# Driver_Converter.net
KiCad netlist of a schematic drawn in Altium Designer
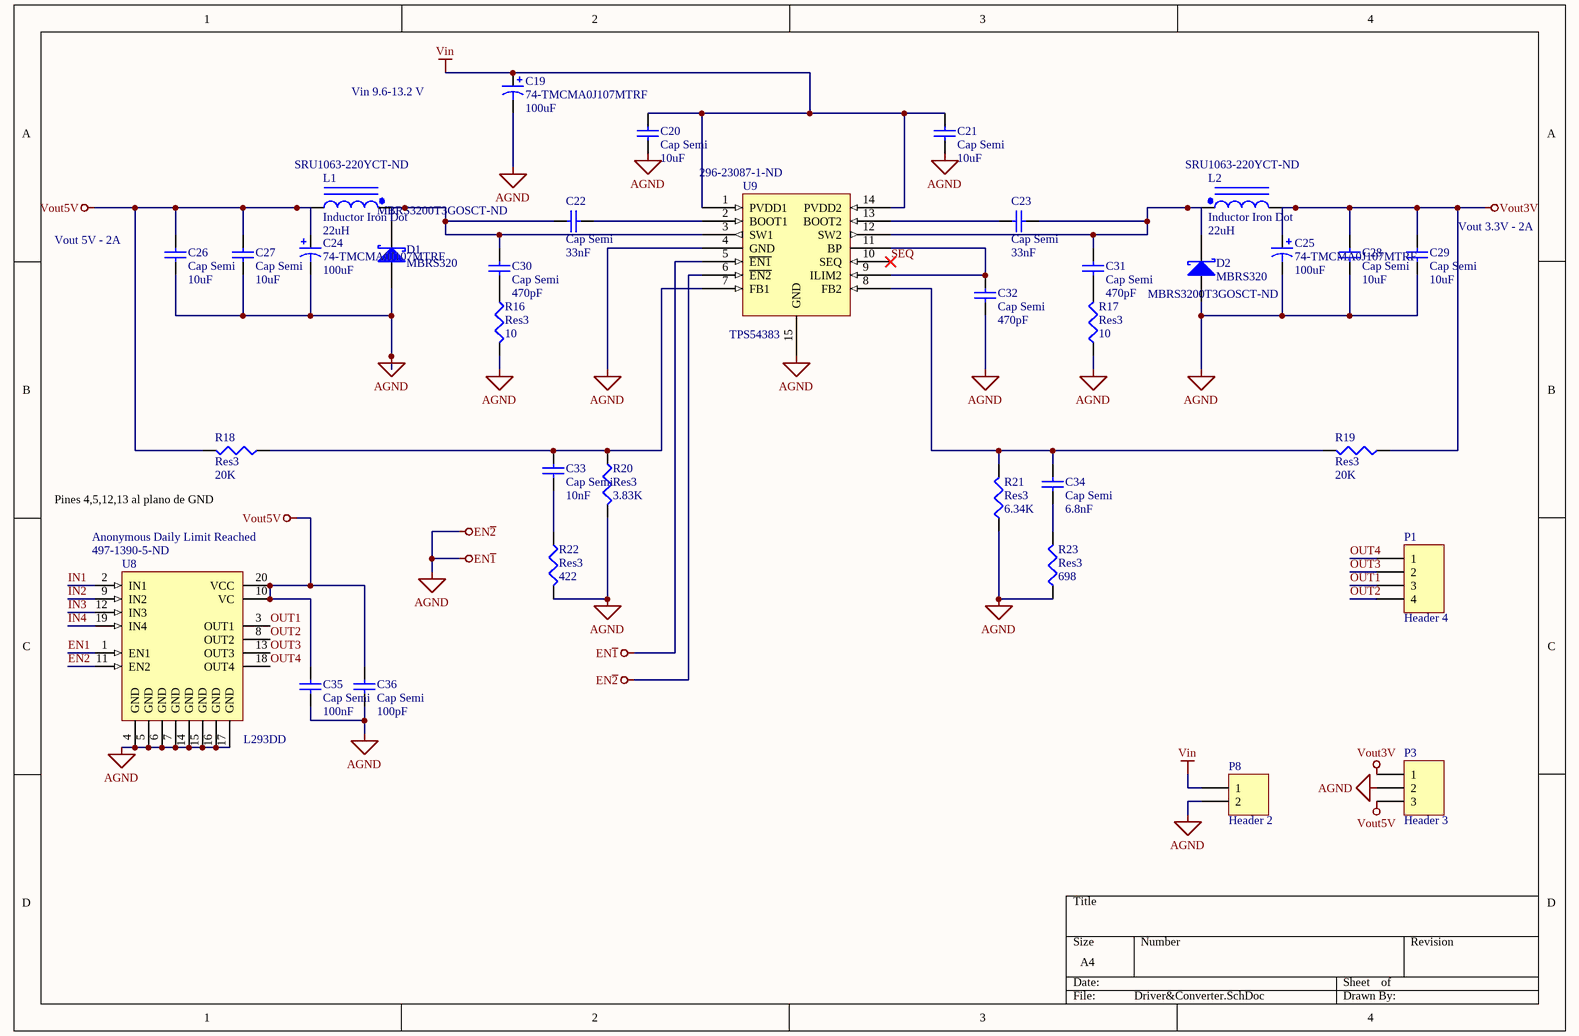
[diagram p0: Driver&Converter.SchDoc]

(export (version "E")
  (design (tool "Eeschema 10.0.6"))
  (components
    (comp (ref "C19")
      (value "74-TMCMA0J107MTRF")
      (footprint "C1206")
      (description "Polarized Capacitor (Surface Mount)")
      (fields (field (name "ALTIUM_VALUE") "100uF") (field (name "PUBLISHER") "Altium Limited"))
      (libsource (lib "Miscellaneous Devices") (part "Cap Pol3"))
    )
    (comp (ref "C20")
      (value "Cap Semi")
      (footprint "C1206")
      (description "Capacitor (Semiconductor SIM Model)")
      (fields (field (name "ALTIUM_VALUE") "10uF") (field (name "PUBLISHER") "Altium Limited"))
      (libsource (lib "Miscellaneous Devices") (part "Cap Semi"))
    )
    (comp (ref "C21")
      (value "Cap Semi")
      (footprint "C1206")
      (description "Capacitor (Semiconductor SIM Model)")
      (fields (field (name "ALTIUM_VALUE") "10uF") (field (name "PUBLISHER") "Altium Limited"))
      (libsource (lib "Miscellaneous Devices") (part "Cap Semi"))
    )
    (comp (ref "C22")
      (value "Cap Semi")
      (footprint "C1206")
      (description "Capacitor (Semiconductor SIM Model)")
      (fields (field (name "ALTIUM_VALUE") "33nF") (field (name "PUBLISHER") "Altium Limited"))
      (libsource (lib "Miscellaneous Devices") (part "Cap Semi"))
    )
    (comp (ref "C23")
      (value "Cap Semi")
      (footprint "C1206")
      (description "Capacitor (Semiconductor SIM Model)")
      (fields (field (name "ALTIUM_VALUE") "33nF") (field (name "PUBLISHER") "Altium Limited"))
      (libsource (lib "Miscellaneous Devices") (part "Cap Semi"))
    )
    (comp (ref "C24")
      (value "74-TMCMA0J107MTRF")
      (footprint "C1206")
      (description "Polarized Capacitor (Surface Mount)")
      (fields (field (name "ALTIUM_VALUE") "100uF") (field (name "PUBLISHER") "Altium Limited"))
      (libsource (lib "") (part "Cap Pol3_1"))
    )
    (comp (ref "C25")
      (value "74-TMCMA0J107MTRF")
      (footprint "C1206")
      (description "Polarized Capacitor (Surface Mount)")
      (fields (field (name "ALTIUM_VALUE") "100uF") (field (name "PUBLISHER") "Altium Limited"))
      (libsource (lib "Miscellaneous Devices") (part "Cap Pol3"))
    )
    (comp (ref "C26")
      (value "Cap Semi")
      (footprint "C1206")
      (description "Capacitor (Semiconductor SIM Model)")
      (fields (field (name "ALTIUM_VALUE") "10uF") (field (name "PUBLISHER") "Altium Limited"))
      (libsource (lib "Miscellaneous Devices") (part "Cap Semi"))
    )
    (comp (ref "C27")
      (value "Cap Semi")
      (footprint "C1206")
      (description "Capacitor (Semiconductor SIM Model)")
      (fields (field (name "ALTIUM_VALUE") "10uF") (field (name "PUBLISHER") "Altium Limited"))
      (libsource (lib "Miscellaneous Devices") (part "Cap Semi"))
    )
    (comp (ref "C28")
      (value "Cap Semi")
      (footprint "C1206")
      (description "Capacitor (Semiconductor SIM Model)")
      (fields (field (name "ALTIUM_VALUE") "10uF") (field (name "PUBLISHER") "Altium Limited"))
      (libsource (lib "Miscellaneous Devices") (part "Cap Semi"))
    )
    (comp (ref "C29")
      (value "Cap Semi")
      (footprint "C1206")
      (description "Capacitor (Semiconductor SIM Model)")
      (fields (field (name "ALTIUM_VALUE") "10uF") (field (name "PUBLISHER") "Altium Limited"))
      (libsource (lib "Miscellaneous Devices") (part "Cap Semi"))
    )
    (comp (ref "C30")
      (value "Cap Semi")
      (footprint "C1206")
      (description "Capacitor (Semiconductor SIM Model)")
      (fields (field (name "ALTIUM_VALUE") "470pF") (field (name "PUBLISHER") "Altium Limited"))
      (libsource (lib "Miscellaneous Devices") (part "Cap Semi"))
    )
    (comp (ref "C31")
      (value "Cap Semi")
      (footprint "C1206")
      (description "Capacitor (Semiconductor SIM Model)")
      (fields (field (name "ALTIUM_VALUE") "470pF") (field (name "PUBLISHER") "Altium Limited"))
      (libsource (lib "Miscellaneous Devices") (part "Cap Semi"))
    )
    (comp (ref "C32")
      (value "Cap Semi")
      (footprint "C1206")
      (description "Capacitor (Semiconductor SIM Model)")
      (fields (field (name "ALTIUM_VALUE") "470pF") (field (name "PUBLISHER") "Altium Limited"))
      (libsource (lib "Miscellaneous Devices") (part "Cap Semi"))
    )
    (comp (ref "C33")
      (value "Cap Semi")
      (footprint "C1206")
      (description "Capacitor (Semiconductor SIM Model)")
      (fields (field (name "ALTIUM_VALUE") "10nF") (field (name "PUBLISHER") "Altium Limited"))
      (libsource (lib "Miscellaneous Devices") (part "Cap Semi"))
    )
    (comp (ref "C34")
      (value "Cap Semi")
      (footprint "C1206")
      (description "Capacitor (Semiconductor SIM Model)")
      (fields (field (name "ALTIUM_VALUE") "6.8nF") (field (name "PUBLISHER") "Altium Limited"))
      (libsource (lib "Miscellaneous Devices") (part "Cap Semi"))
    )
    (comp (ref "C35")
      (value "Cap Semi")
      (footprint "C1206")
      (description "Capacitor (Semiconductor SIM Model)")
      (fields (field (name "ALTIUM_VALUE") "100nF") (field (name "PUBLISHER") "Altium Limited"))
      (libsource (lib "Miscellaneous Devices") (part "Cap Semi"))
    )
    (comp (ref "C36")
      (value "Cap Semi")
      (footprint "C1206")
      (description "Capacitor (Semiconductor SIM Model)")
      (fields (field (name "ALTIUM_VALUE") "100pF") (field (name "PUBLISHER") "Altium Limited"))
      (libsource (lib "Miscellaneous Devices") (part "Cap Semi"))
    )
    (comp (ref "D1")
      (value "MBRS320")
      (footprint "SMB")
      (description "Schottky Diode")
      (fields
        (field (name "SUPPLIER PART NUMBER 1") "MBRS3200T3GOSCT-ND")
        (field (name "PUBLISHER") "Altium Limited")
      )
      (libsource (lib "Miscellaneous Devices") (part "D Schottky"))
    )
    (comp (ref "D2")
      (value "MBRS320")
      (footprint "SMB")
      (description "Schottky Diode")
      (fields
        (field (name "SUPPLIER PART NUMBER 1") "MBRS3200T3GOSCT-ND")
        (field (name "PUBLISHER") "Altium Limited")
      )
      (libsource (lib "Miscellaneous Devices") (part "D Schottky"))
    )
    (comp (ref "L1")
      (value "Inductor Iron Dot")
      (footprint "DIODE_SMC")
      (description "Magnetic-Core Inductor with Winding Polarity Marking")
      (fields
        (field (name "ALTIUM_VALUE") "22uH")
        (field (name "SUPPLIER PART NUMBER 1") "SRU1063-220YCT-ND")
        (field (name "PUBLISHER") "Altium Limited")
      )
      (libsource (lib "") (part "Inductor Iron Dot_1"))
    )
    (comp (ref "L2")
      (value "Inductor Iron Dot")
      (footprint "DIODE_SMC")
      (description "Magnetic-Core Inductor with Winding Polarity Marking")
      (fields
        (field (name "ALTIUM_VALUE") "22uH")
        (field (name "SUPPLIER PART NUMBER 1") "SRU1063-220YCT-ND")
        (field (name "PUBLISHER") "Altium Limited")
      )
      (libsource (lib "Miscellaneous Devices") (part "Inductor Iron Dot"))
    )
    (comp (ref "P1")
      (value "Header 4")
      (footprint "HDR1X4")
      (description "Header, 4-Pin")
      (fields (field (name "PUBLISHER") "Altium Limited"))
      (libsource (lib "Miscellaneous Connectors") (part "Header 4"))
    )
    (comp (ref "P3")
      (value "Header 3")
      (footprint "HDR1X3")
      (description "Header, 3-Pin")
      (fields (field (name "PUBLISHER") "Altium Limited"))
      (libsource (lib "Miscellaneous Connectors") (part "Header 3"))
    )
    (comp (ref "P8")
      (value "Header 2")
      (footprint "HDR1X2")
      (description "Header, 2-Pin")
      (fields (field (name "PUBLISHER") "Altium Limited"))
      (libsource (lib "Miscellaneous Connectors") (part "Header 2"))
    )
    (comp (ref "R16")
      (value "Res3")
      (footprint "J1-0603")
      (description "Resistor")
      (fields (field (name "ALTIUM_VALUE") "10") (field (name "PUBLISHER") "Altium Limited"))
      (libsource (lib "Miscellaneous Devices") (part "Res3"))
    )
    (comp (ref "R17")
      (value "Res3")
      (footprint "J1-0603")
      (description "Resistor")
      (fields (field (name "ALTIUM_VALUE") "10") (field (name "PUBLISHER") "Altium Limited"))
      (libsource (lib "Miscellaneous Devices") (part "Res3"))
    )
    (comp (ref "R18")
      (value "Res3")
      (footprint "J1-0603")
      (description "Resistor")
      (fields (field (name "ALTIUM_VALUE") "20K") (field (name "PUBLISHER") "Altium Limited"))
      (libsource (lib "Miscellaneous Devices") (part "Res3"))
    )
    (comp (ref "R19")
      (value "Res3")
      (footprint "J1-0603")
      (description "Resistor")
      (fields (field (name "ALTIUM_VALUE") "20K") (field (name "PUBLISHER") "Altium Limited"))
      (libsource (lib "Miscellaneous Devices") (part "Res3"))
    )
    (comp (ref "R20")
      (value "Res3")
      (footprint "J1-0603")
      (description "Resistor")
      (fields (field (name "ALTIUM_VALUE") "3.83K") (field (name "PUBLISHER") "Altium Limited"))
      (libsource (lib "Miscellaneous Devices") (part "Res3"))
    )
    (comp (ref "R21")
      (value "Res3")
      (footprint "J1-0603")
      (description "Resistor")
      (fields (field (name "ALTIUM_VALUE") "6.34K") (field (name "PUBLISHER") "Altium Limited"))
      (libsource (lib "Miscellaneous Devices") (part "Res3"))
    )
    (comp (ref "R22")
      (value "Res3")
      (footprint "J1-0603")
      (description "Resistor")
      (fields (field (name "ALTIUM_VALUE") "422") (field (name "PUBLISHER") "Altium Limited"))
      (libsource (lib "Miscellaneous Devices") (part "Res3"))
    )
    (comp (ref "R23")
      (value "Res3")
      (footprint "J1-0603")
      (description "Resistor")
      (fields (field (name "ALTIUM_VALUE") "698") (field (name "PUBLISHER") "Altium Limited"))
      (libsource (lib "Miscellaneous Devices") (part "Res3"))
    )
    (comp (ref "U8")
      (value "L293DD")
      (footprint "SO20_N")
      (description "Push-Pull Four Channel Driver With Diode")
      (fields
        (field (name "SUPPLIER PART NUMBER 1") "497-1390-5-ND")
        (field (name "SUPPLIER PART NUMBER 2") "Anonymous Daily Limit Reached")
        (field (name "PUBLISHER") "Altium Limited")
      )
      (libsource (lib "ST Interface DC & Stepper Motor Controller") (part "L293DD"))
    )
    (comp (ref "U9")
      (value "TPS54383")
      (footprint "TPS54383_converter")
      (fields (field (name "SUPPLIER PART NUMBER 1") "296-23087-1-ND"))
      (libsource (lib "TPS54383") (part "TPS54383"))
    )
  )
  (nets
    (net (code "1") (name "/EN1") (class "Default")
      (node (ref "U8") (pin "1") (pinfunction "EN1_1") (pintype "input"))
    )
    (net (code "2") (name "/EN2") (class "Default")
      (node (ref "U8") (pin "11") (pinfunction "EN2_11") (pintype "input"))
    )
    (net (code "3") (name "/IN1") (class "Default")
      (node (ref "U8") (pin "2") (pinfunction "IN1_2") (pintype "input"))
    )
    (net (code "4") (name "/IN2") (class "Default")
      (node (ref "U8") (pin "9") (pinfunction "IN2_9") (pintype "input"))
    )
    (net (code "5") (name "/IN3") (class "Default")
      (node (ref "U8") (pin "12") (pinfunction "IN3_12") (pintype "input"))
    )
    (net (code "6") (name "/IN4") (class "Default")
      (node (ref "U8") (pin "19") (pinfunction "IN4_19") (pintype "input"))
    )
    (net (code "7") (name "/OUT1") (class "Default")
      (node (ref "P1") (pin "3") (pinfunction "3_3") (pintype "passive"))
      (node (ref "U8") (pin "3") (pinfunction "OUT1_3") (pintype "tri_state"))
    )
    (net (code "8") (name "/OUT2") (class "Default")
      (node (ref "P1") (pin "4") (pinfunction "4_4") (pintype "passive"))
      (node (ref "U8") (pin "8") (pinfunction "OUT2_8") (pintype "tri_state"))
    )
    (net (code "9") (name "/OUT3") (class "Default")
      (node (ref "P1") (pin "2") (pinfunction "2_2") (pintype "passive"))
      (node (ref "U8") (pin "13") (pinfunction "OUT3_13") (pintype "tri_state"))
    )
    (net (code "10") (name "/OUT4") (class "Default")
      (node (ref "P1") (pin "1") (pinfunction "1_1") (pintype "passive"))
      (node (ref "U8") (pin "18") (pinfunction "OUT4_18") (pintype "tri_state"))
    )
    (net (code "11") (name "/SEQ") (class "Default")
      (node (ref "U9") (pin "10") (pinfunction "SEQ_10") (pintype "input+no_connect"))
    )
    (net (code "12") (name "AGND") (class "Default")
      (node (ref "C19") (pin "2") (pinfunction "2_2") (pintype "passive"))
      (node (ref "C20") (pin "1") (pinfunction "1_1") (pintype "passive"))
      (node (ref "C21") (pin "1") (pinfunction "1_1") (pintype "passive"))
      (node (ref "C24") (pin "2") (pinfunction "2_2") (pintype "passive"))
      (node (ref "C25") (pin "2") (pinfunction "2_2") (pintype "passive"))
      (node (ref "C26") (pin "1") (pinfunction "1_1") (pintype "passive"))
      (node (ref "C27") (pin "1") (pinfunction "1_1") (pintype "passive"))
      (node (ref "C28") (pin "1") (pinfunction "1_1") (pintype "passive"))
      (node (ref "C29") (pin "1") (pinfunction "1_1") (pintype "passive"))
      (node (ref "C32") (pin "1") (pinfunction "1_1") (pintype "passive"))
      (node (ref "C35") (pin "1") (pinfunction "1_1") (pintype "passive"))
      (node (ref "C36") (pin "1") (pinfunction "1_1") (pintype "passive"))
      (node (ref "D1") (pin "1") (pinfunction "A_1") (pintype "passive"))
      (node (ref "D2") (pin "1") (pinfunction "A_1") (pintype "passive"))
      (node (ref "P3") (pin "2") (pinfunction "2_2") (pintype "passive"))
      (node (ref "P8") (pin "2") (pinfunction "2_2") (pintype "passive"))
      (node (ref "R16") (pin "1") (pinfunction "1_1") (pintype "passive"))
      (node (ref "R17") (pin "1") (pinfunction "1_1") (pintype "passive"))
      (node (ref "R20") (pin "1") (pinfunction "1_1") (pintype "passive"))
      (node (ref "R21") (pin "1") (pinfunction "1_1") (pintype "passive"))
      (node (ref "R22") (pin "1") (pinfunction "1_1") (pintype "passive"))
      (node (ref "R23") (pin "1") (pinfunction "1_1") (pintype "passive"))
      (node (ref "U8") (pin "14") (pinfunction "GND_14") (pintype "power_in"))
      (node (ref "U8") (pin "15") (pinfunction "GND_15") (pintype "power_in"))
      (node (ref "U8") (pin "16") (pinfunction "GND_16") (pintype "power_in"))
      (node (ref "U8") (pin "17") (pinfunction "GND_17") (pintype "power_in"))
      (node (ref "U8") (pin "4") (pinfunction "GND_4") (pintype "power_in"))
      (node (ref "U8") (pin "5") (pinfunction "GND_5") (pintype "power_in"))
      (node (ref "U8") (pin "6") (pinfunction "GND_6") (pintype "power_in"))
      (node (ref "U8") (pin "7") (pinfunction "GND_7") (pintype "power_in"))
      (node (ref "U9") (pin "15") (pinfunction "GND_15") (pintype "passive"))
      (node (ref "U9") (pin "4") (pinfunction "GND_4") (pintype "passive"))
      (node (ref "U9") (pin "5") (pinfunction "~{EN1}_5") (pintype "input"))
      (node (ref "U9") (pin "6") (pinfunction "~{EN2}_6") (pintype "input"))
    )
    (net (code "13") (name "Net-(C30-Pad1)") (class "Default")
      (node (ref "C30") (pin "1") (pinfunction "1_1") (pintype "passive"))
      (node (ref "R16") (pin "2") (pinfunction "2_2") (pintype "passive"))
    )
    (net (code "14") (name "Net-(C31-Pad1)") (class "Default")
      (node (ref "C31") (pin "1") (pinfunction "1_1") (pintype "passive"))
      (node (ref "R17") (pin "2") (pinfunction "2_2") (pintype "passive"))
    )
    (net (code "15") (name "Net-(C33-Pad1)") (class "Default")
      (node (ref "C33") (pin "1") (pinfunction "1_1") (pintype "passive"))
      (node (ref "R22") (pin "2") (pinfunction "2_2") (pintype "passive"))
    )
    (net (code "16") (name "Net-(C34-Pad1)") (class "Default")
      (node (ref "C34") (pin "1") (pinfunction "1_1") (pintype "passive"))
      (node (ref "R23") (pin "2") (pinfunction "2_2") (pintype "passive"))
    )
    (net (code "17") (name "Net-(D1-K)") (class "Default")
      (node (ref "C22") (pin "1") (pinfunction "1_1") (pintype "passive"))
      (node (ref "C30") (pin "2") (pinfunction "2_2") (pintype "passive"))
      (node (ref "D1") (pin "2") (pinfunction "K_2") (pintype "passive"))
      (node (ref "L1") (pin "1") (pinfunction "1_1") (pintype "passive"))
      (node (ref "U9") (pin "3") (pinfunction "SW1_3") (pintype "output"))
    )
    (net (code "18") (name "Net-(D2-K)") (class "Default")
      (node (ref "C23") (pin "1") (pinfunction "1_1") (pintype "passive"))
      (node (ref "C31") (pin "2") (pinfunction "2_2") (pintype "passive"))
      (node (ref "D2") (pin "2") (pinfunction "K_2") (pintype "passive"))
      (node (ref "L2") (pin "1") (pinfunction "1_1") (pintype "passive"))
      (node (ref "U9") (pin "12") (pinfunction "SW2_12") (pintype "output"))
    )
    (net (code "19") (name "Net-(U9-BOOT1)") (class "Default")
      (node (ref "C22") (pin "2") (pinfunction "2_2") (pintype "passive"))
      (node (ref "U9") (pin "2") (pinfunction "BOOT1_2") (pintype "input"))
    )
    (net (code "20") (name "Net-(U9-BOOT2)") (class "Default")
      (node (ref "C23") (pin "2") (pinfunction "2_2") (pintype "passive"))
      (node (ref "U9") (pin "13") (pinfunction "BOOT2_13") (pintype "input"))
    )
    (net (code "21") (name "Net-(U9-BP)") (class "Default")
      (node (ref "C32") (pin "2") (pinfunction "2_2") (pintype "passive"))
      (node (ref "U9") (pin "11") (pinfunction "BP_11") (pintype "passive"))
      (node (ref "U9") (pin "9") (pinfunction "ILIM2_9") (pintype "input"))
    )
    (net (code "22") (name "Net-(U9-FB1)") (class "Default")
      (node (ref "C33") (pin "2") (pinfunction "2_2") (pintype "passive"))
      (node (ref "R18") (pin "2") (pinfunction "2_2") (pintype "passive"))
      (node (ref "R20") (pin "2") (pinfunction "2_2") (pintype "passive"))
      (node (ref "U9") (pin "7") (pinfunction "FB1_7") (pintype "input"))
    )
    (net (code "23") (name "Net-(U9-FB2)") (class "Default")
      (node (ref "C34") (pin "2") (pinfunction "2_2") (pintype "passive"))
      (node (ref "R19") (pin "2") (pinfunction "2_2") (pintype "passive"))
      (node (ref "R21") (pin "2") (pinfunction "2_2") (pintype "passive"))
      (node (ref "U9") (pin "8") (pinfunction "FB2_8") (pintype "input"))
    )
    (net (code "24") (name "Vin") (class "Default")
      (node (ref "C19") (pin "1") (pinfunction "1_1") (pintype "passive"))
      (node (ref "C20") (pin "2") (pinfunction "2_2") (pintype "passive"))
      (node (ref "C21") (pin "2") (pinfunction "2_2") (pintype "passive"))
      (node (ref "P8") (pin "1") (pinfunction "1_1") (pintype "passive"))
      (node (ref "U9") (pin "1") (pinfunction "PVDD1_1") (pintype "input"))
      (node (ref "U9") (pin "14") (pinfunction "PVDD2_14") (pintype "input"))
    )
    (net (code "25") (name "Vout3V") (class "Default")
      (node (ref "C25") (pin "1") (pinfunction "1_1") (pintype "passive"))
      (node (ref "C28") (pin "2") (pinfunction "2_2") (pintype "passive"))
      (node (ref "C29") (pin "2") (pinfunction "2_2") (pintype "passive"))
      (node (ref "L2") (pin "2") (pinfunction "2_2") (pintype "passive"))
      (node (ref "P3") (pin "1") (pinfunction "1_1") (pintype "passive"))
      (node (ref "R19") (pin "1") (pinfunction "1_1") (pintype "passive"))
    )
    (net (code "26") (name "Vout5V") (class "Default")
      (node (ref "C24") (pin "1") (pinfunction "1_1") (pintype "passive"))
      (node (ref "C26") (pin "2") (pinfunction "2_2") (pintype "passive"))
      (node (ref "C27") (pin "2") (pinfunction "2_2") (pintype "passive"))
      (node (ref "C35") (pin "2") (pinfunction "2_2") (pintype "passive"))
      (node (ref "C36") (pin "2") (pinfunction "2_2") (pintype "passive"))
      (node (ref "L1") (pin "2") (pinfunction "2_2") (pintype "passive"))
      (node (ref "P3") (pin "3") (pinfunction "3_3") (pintype "passive"))
      (node (ref "R18") (pin "1") (pinfunction "1_1") (pintype "passive"))
      (node (ref "U8") (pin "10") (pinfunction "VC_10") (pintype "power_in"))
      (node (ref "U8") (pin "20") (pinfunction "VCC_20") (pintype "power_in"))
    )
  )
)
